# measurement-output-hw.net
KiCad netlist of a schematic drawn in Altium Designer
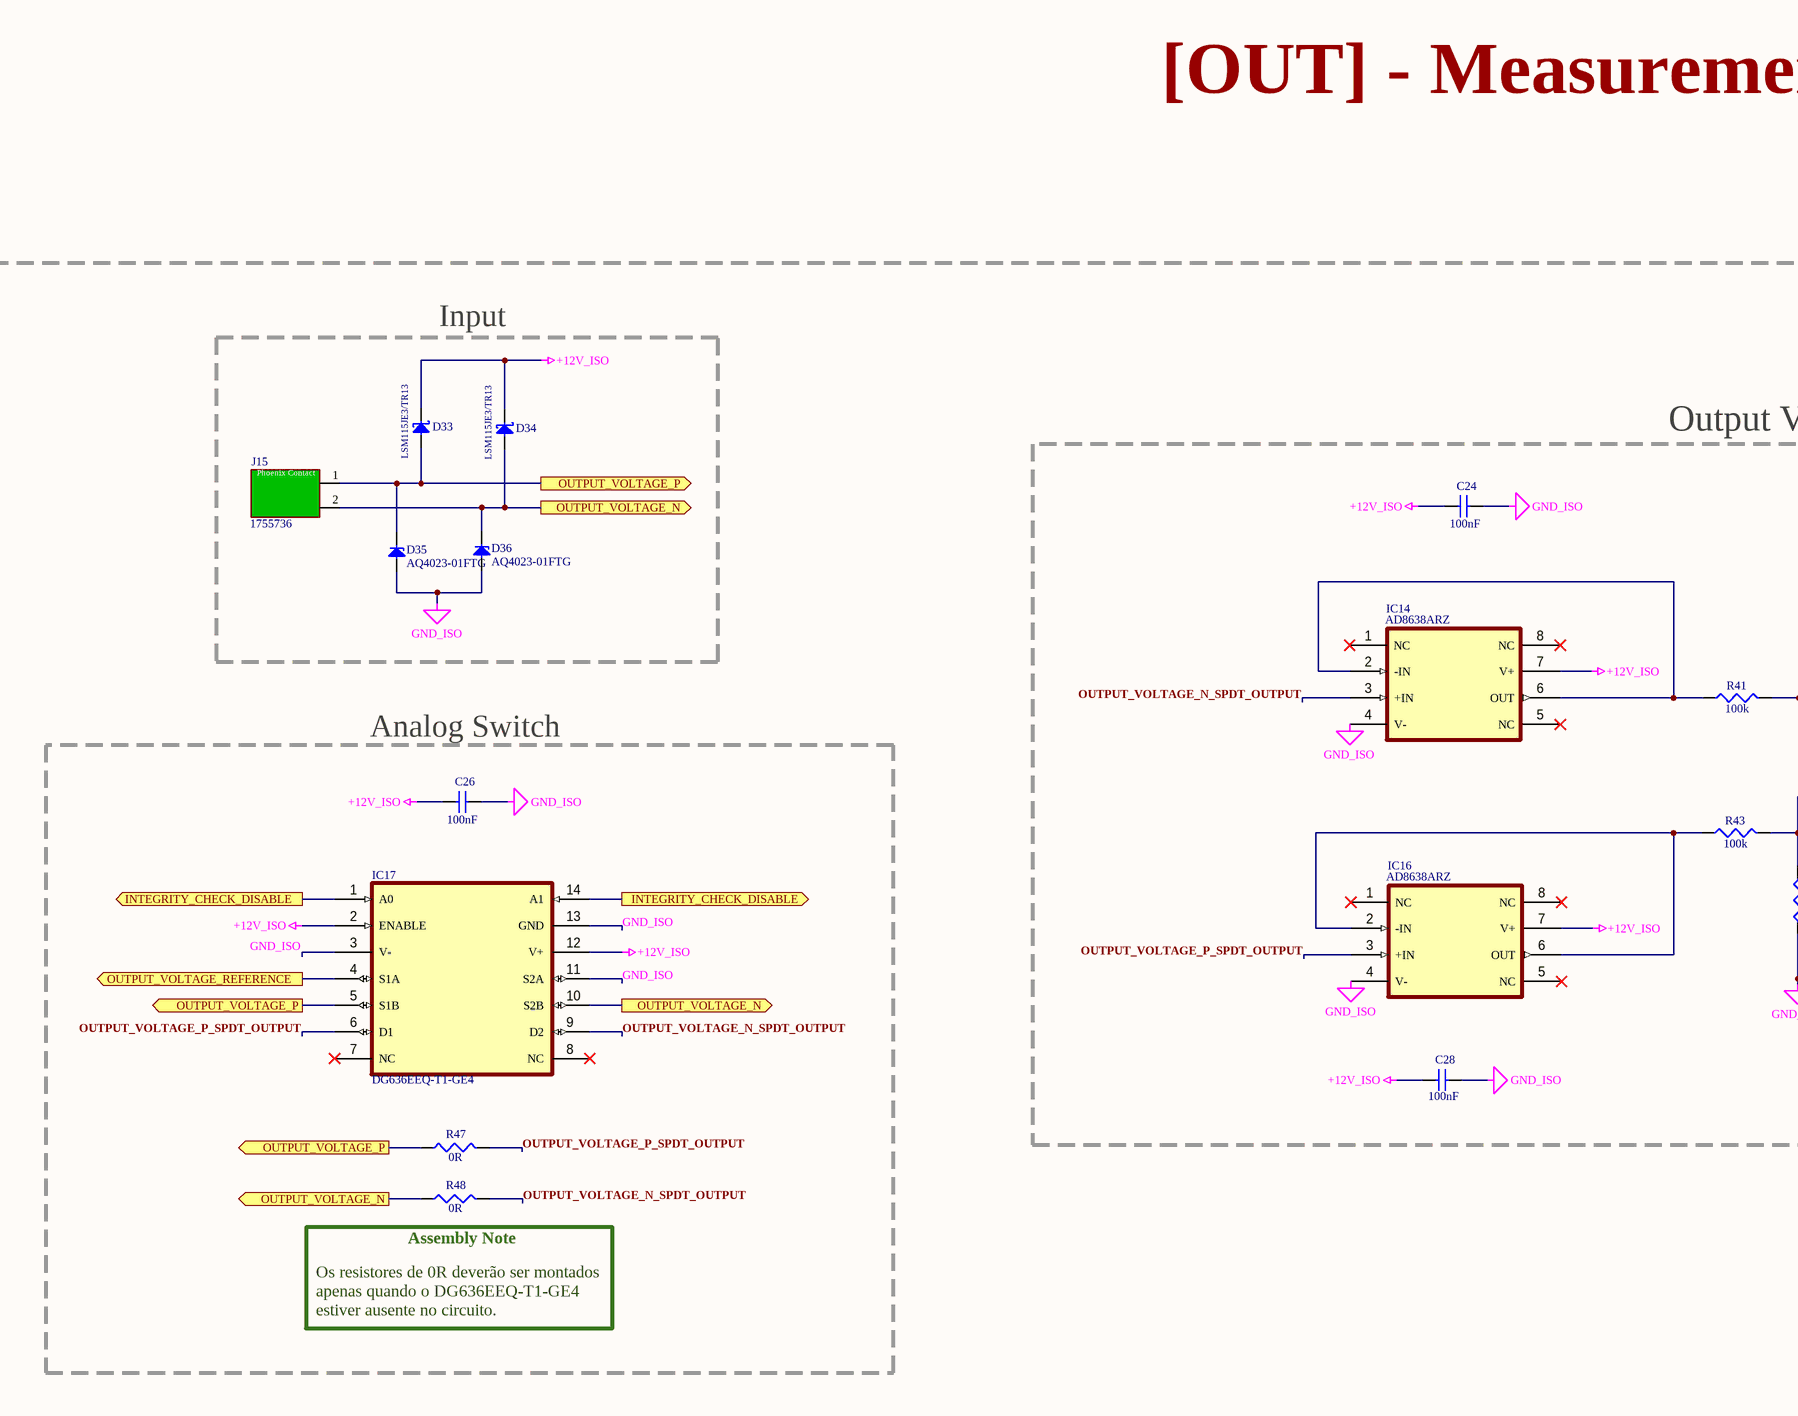
[diagram p0: measurement-output-hw.SchDoc, top left]
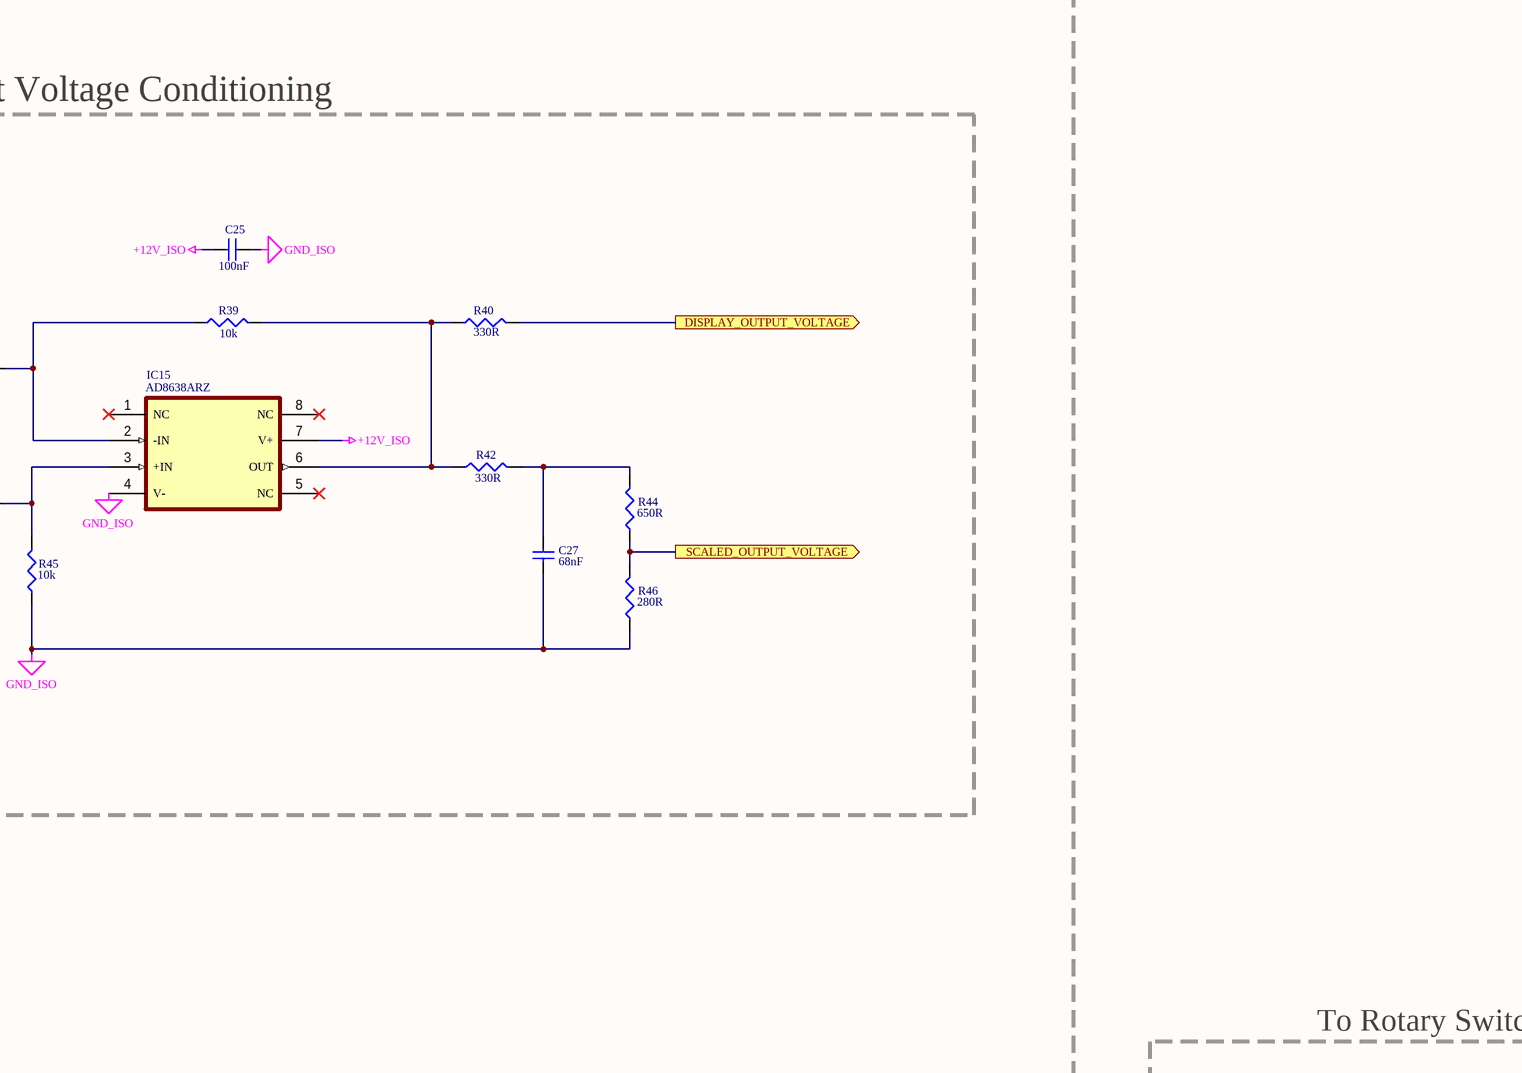
[diagram p1: measurement-output-hw.SchDoc, top right]
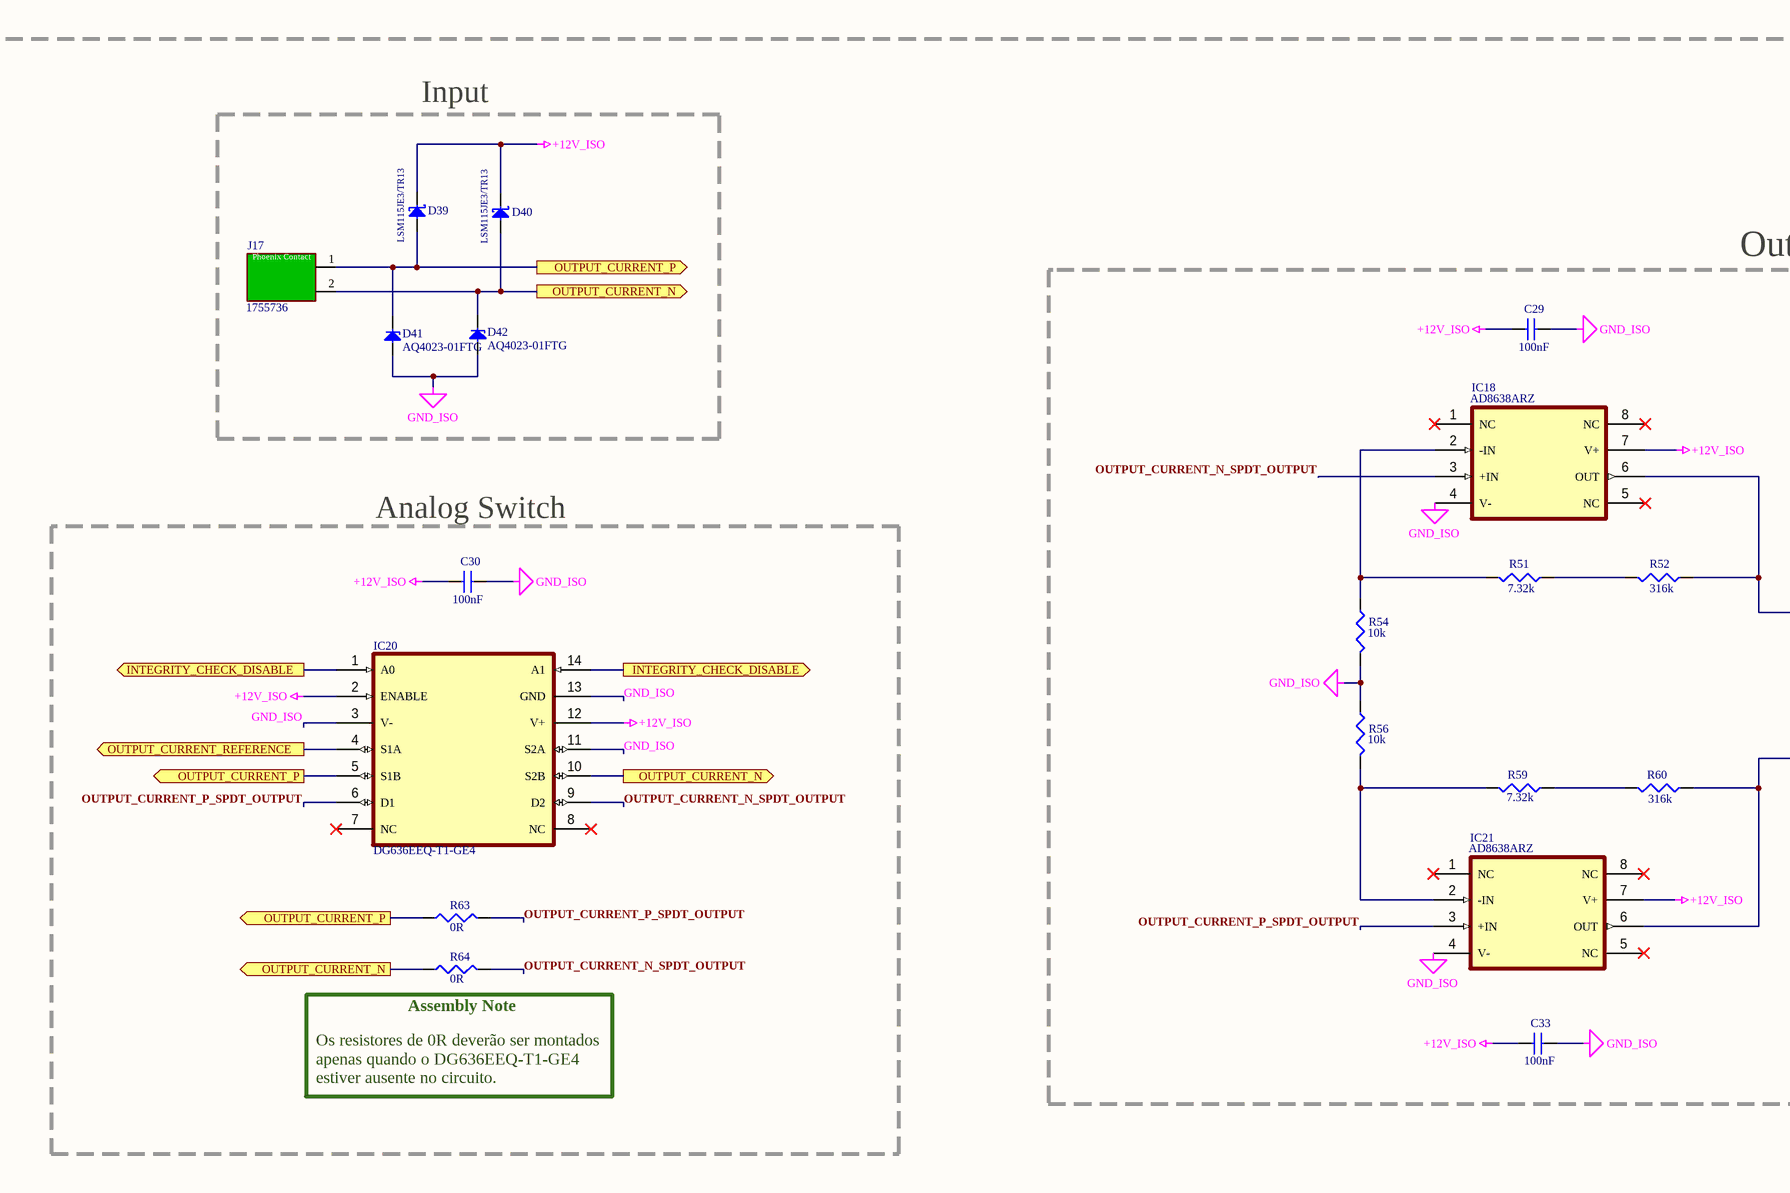
[diagram p2: measurement-output-hw.SchDoc, bottom left]
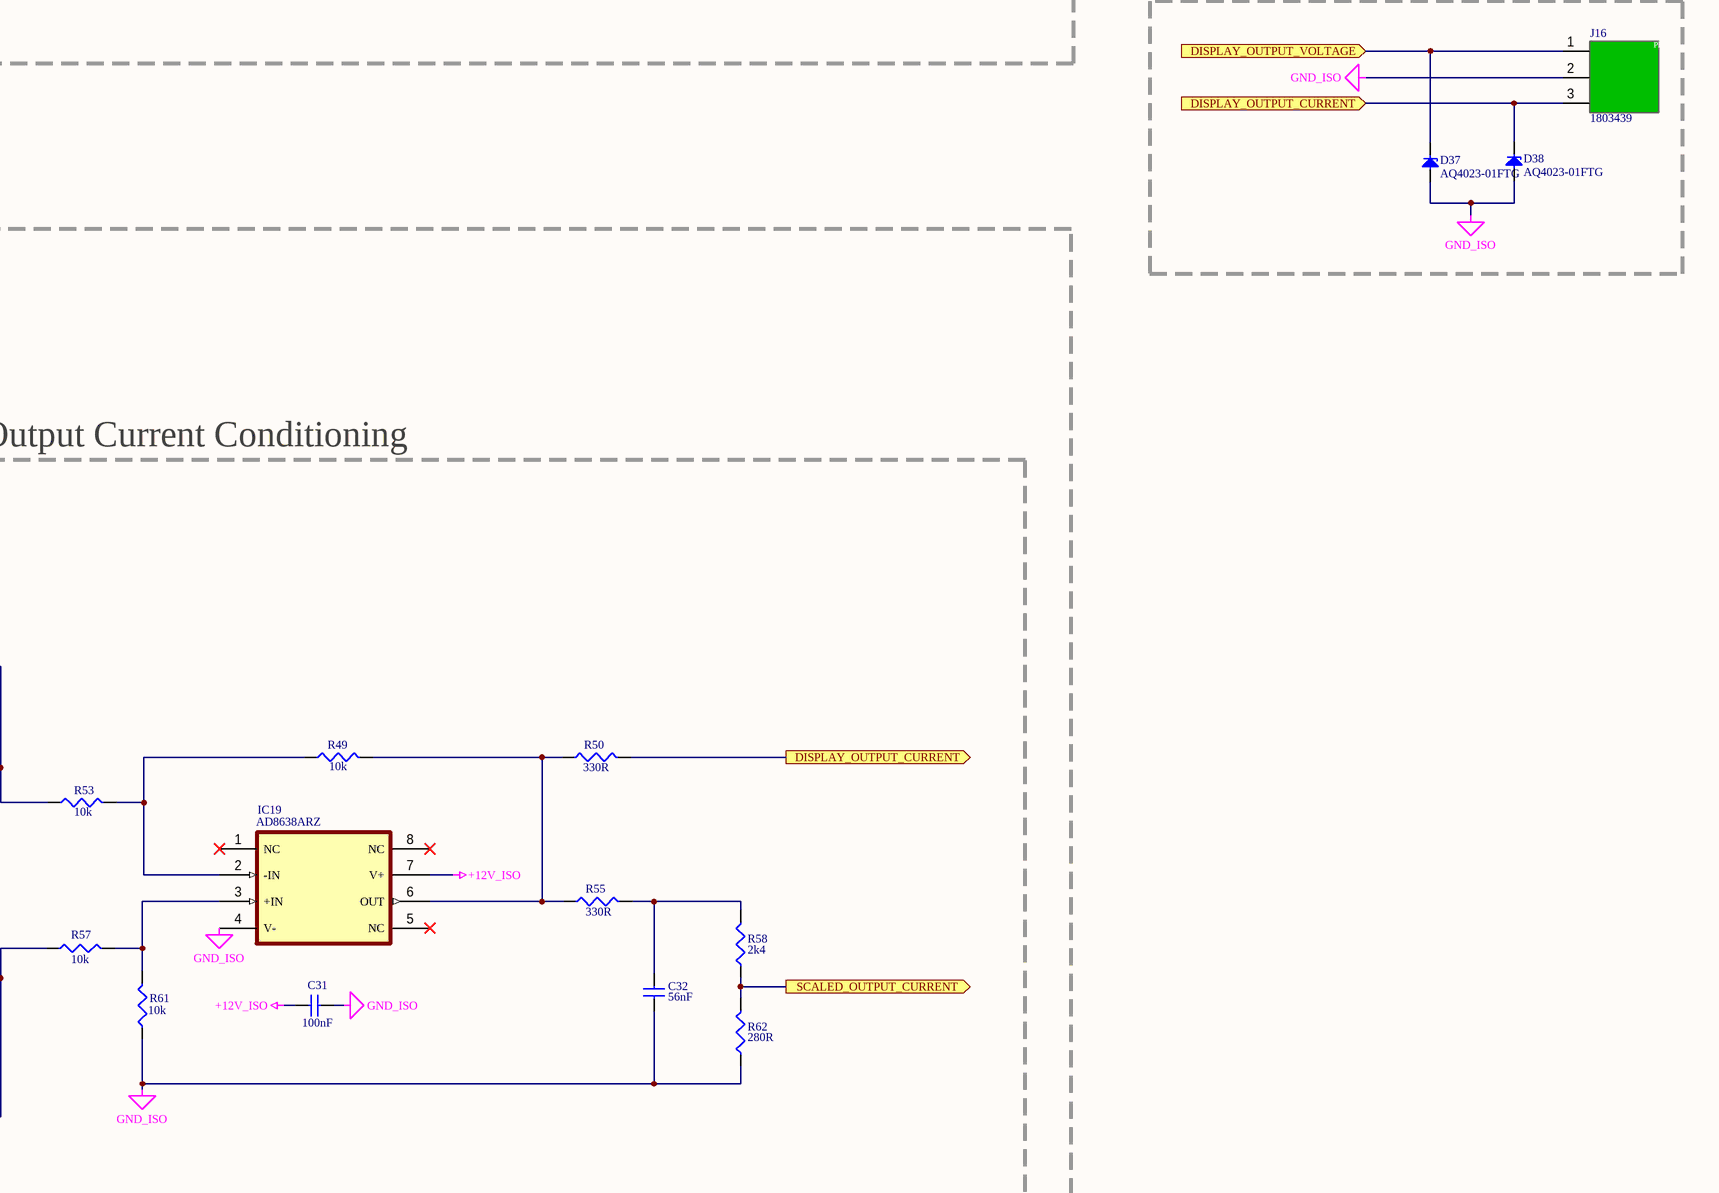
[diagram p3: measurement-output-hw.SchDoc, bottom right]

(export (version "E")
  (design (tool "Eeschema 10.0.6"))
  (components
    (comp (ref "C24")
      (value "100nF")
      (footprint "C0805")
      (libsource (lib "acopians-powerspy-monitoring-hw-library-schematic") (part "Capacitor 100nF"))
    )
    (comp (ref "C25")
      (value "100nF")
      (footprint "C0805")
      (libsource (lib "acopians-powerspy-monitoring-hw-library-schematic") (part "Capacitor 100nF"))
    )
    (comp (ref "C26")
      (value "100nF")
      (footprint "C0805")
      (libsource (lib "acopians-powerspy-monitoring-hw-library-schematic") (part "Capacitor 100nF"))
    )
    (comp (ref "C27")
      (value "68nF")
      (footprint "C0805")
      (libsource (lib "acopians-powerspy-monitoring-hw-library-schematic") (part "Capacitor 68nF"))
    )
    (comp (ref "C28")
      (value "100nF")
      (footprint "C0805")
      (libsource (lib "acopians-powerspy-monitoring-hw-library-schematic") (part "Capacitor 100nF"))
    )
    (comp (ref "C29")
      (value "100nF")
      (footprint "C0805")
      (libsource (lib "acopians-powerspy-monitoring-hw-library-schematic") (part "Capacitor 100nF"))
    )
    (comp (ref "C30")
      (value "100nF")
      (footprint "C0805")
      (libsource (lib "acopians-powerspy-monitoring-hw-library-schematic") (part "Capacitor 100nF"))
    )
    (comp (ref "C31")
      (value "100nF")
      (footprint "C0805")
      (libsource (lib "acopians-powerspy-monitoring-hw-library-schematic") (part "Capacitor 100nF"))
    )
    (comp (ref "C32")
      (value "56nF")
      (footprint "C0805")
      (libsource (lib "acopians-powerspy-monitoring-hw-library-schematic") (part "Capacitor 56nF"))
    )
    (comp (ref "C33")
      (value "100nF")
      (footprint "C0805")
      (libsource (lib "acopians-powerspy-monitoring-hw-library-schematic") (part "Capacitor 100nF"))
    )
    (comp (ref "D33")
      (value "LSM115JE3/TR13")
      (footprint "DO-214BA")
      (description "DIODE SCHOTTKY 15V, 1A, DO214BA")
      (libsource (lib "acopians-powerspy-monitoring-hw-library-schematic") (part "LSM115JE3/TR13"))
    )
    (comp (ref "D34")
      (value "LSM115JE3/TR13")
      (footprint "DO-214BA")
      (description "DIODE SCHOTTKY 15V, 1A, DO214BA")
      (libsource (lib "acopians-powerspy-monitoring-hw-library-schematic") (part "LSM115JE3/TR13"))
    )
    (comp (ref "D35")
      (value "AQ4023-01FTG")
      (footprint "SOD-323")
      (description "Unidirectional TVS DIode, 12A, 1.3pF")
      (libsource (lib "acopians-powerspy-monitoring-hw-library-schematic") (part "AQ4023-01FTG"))
    )
    (comp (ref "D36")
      (value "AQ4023-01FTG")
      (footprint "SOD-323")
      (description "Unidirectional TVS DIode, 12A, 1.3pF")
      (libsource (lib "acopians-powerspy-monitoring-hw-library-schematic") (part "AQ4023-01FTG"))
    )
    (comp (ref "D37")
      (value "AQ4023-01FTG")
      (footprint "SOD-323")
      (description "Unidirectional TVS DIode, 12A, 1.3pF")
      (libsource (lib "acopians-powerspy-monitoring-hw-library-schematic") (part "AQ4023-01FTG"))
    )
    (comp (ref "D38")
      (value "AQ4023-01FTG")
      (footprint "SOD-323")
      (description "Unidirectional TVS DIode, 12A, 1.3pF")
      (libsource (lib "acopians-powerspy-monitoring-hw-library-schematic") (part "AQ4023-01FTG"))
    )
    (comp (ref "D39")
      (value "LSM115JE3/TR13")
      (footprint "DO-214BA")
      (description "DIODE SCHOTTKY 15V, 1A, DO214BA")
      (libsource (lib "acopians-powerspy-monitoring-hw-library-schematic") (part "LSM115JE3/TR13"))
    )
    (comp (ref "D40")
      (value "LSM115JE3/TR13")
      (footprint "DO-214BA")
      (description "DIODE SCHOTTKY 15V, 1A, DO214BA")
      (libsource (lib "acopians-powerspy-monitoring-hw-library-schematic") (part "LSM115JE3/TR13"))
    )
    (comp (ref "D41")
      (value "AQ4023-01FTG")
      (footprint "SOD-323")
      (description "Unidirectional TVS DIode, 12A, 1.3pF")
      (libsource (lib "acopians-powerspy-monitoring-hw-library-schematic") (part "AQ4023-01FTG"))
    )
    (comp (ref "D42")
      (value "AQ4023-01FTG")
      (footprint "SOD-323")
      (description "Unidirectional TVS DIode, 12A, 1.3pF")
      (libsource (lib "acopians-powerspy-monitoring-hw-library-schematic") (part "AQ4023-01FTG"))
    )
    (comp (ref "IC14")
      (value "AD8638ARZ")
      (footprint "SOIC-8")
      (description "16V, Auto-Zero, Rail-to-Rail Output Operational Amplifiers")
      (libsource (lib "acopians-powerspy-monitoring-hw-library-schematic") (part "AD8638ARZ"))
    )
    (comp (ref "IC15")
      (value "AD8638ARZ")
      (footprint "SOIC-8")
      (description "16V, Auto-Zero, Rail-to-Rail Output Operational Amplifiers")
      (libsource (lib "acopians-powerspy-monitoring-hw-library-schematic") (part "AD8638ARZ"))
    )
    (comp (ref "IC16")
      (value "AD8638ARZ")
      (footprint "SOIC-8")
      (description "16V, Auto-Zero, Rail-to-Rail Output Operational Amplifiers")
      (libsource (lib "acopians-powerspy-monitoring-hw-library-schematic") (part "AD8638ARZ"))
    )
    (comp (ref "IC17")
      (value "DG636EEQ-T1-GE4")
      (footprint "TSSOP-14")
      (description "Analog Switch Dual-SPDT, 14 pins")
      (libsource (lib "acopians-powerspy-monitoring-hw-library-schematic") (part "DG636EEQ-T1-GE4"))
    )
    (comp (ref "IC18")
      (value "AD8638ARZ")
      (footprint "SOIC-8")
      (description "16V, Auto-Zero, Rail-to-Rail Output Operational Amplifiers")
      (libsource (lib "acopians-powerspy-monitoring-hw-library-schematic") (part "AD8638ARZ"))
    )
    (comp (ref "IC19")
      (value "AD8638ARZ")
      (footprint "SOIC-8")
      (description "16V, Auto-Zero, Rail-to-Rail Output Operational Amplifiers")
      (libsource (lib "acopians-powerspy-monitoring-hw-library-schematic") (part "AD8638ARZ"))
    )
    (comp (ref "IC20")
      (value "DG636EEQ-T1-GE4")
      (footprint "TSSOP-14")
      (description "Analog Switch Dual-SPDT, 14 pins")
      (libsource (lib "acopians-powerspy-monitoring-hw-library-schematic") (part "DG636EEQ-T1-GE4"))
    )
    (comp (ref "IC21")
      (value "AD8638ARZ")
      (footprint "SOIC-8")
      (description "16V, Auto-Zero, Rail-to-Rail Output Operational Amplifiers")
      (libsource (lib "acopians-powerspy-monitoring-hw-library-schematic") (part "AD8638ARZ"))
    )
    (comp (ref "J15")
      (value "1755736")
      (footprint "Conector 2 vias")
      (description "Term Block HDR 2POS VERT 5.08MM")
      (libsource (lib "acopians-powerspy-monitoring-hw-library-schematic") (part "Phoenix 1755736"))
    )
    (comp (ref "J16")
      (value "1803439")
      (footprint "Conector Phoenix 3 vias")
      (libsource (lib "acopians-powerspy-monitoring-hw-library-schematic") (part "Conector Phoenix 3 vias"))
    )
    (comp (ref "J17")
      (value "1755736")
      (footprint "Conector 2 vias")
      (description "Term Block HDR 2POS VERT 5.08MM")
      (libsource (lib "acopians-powerspy-monitoring-hw-library-schematic") (part "Phoenix 1755736"))
    )
    (comp (ref "R39")
      (value "10k")
      (footprint "Resistor 0805")
      (libsource (lib "acopians-powerspy-monitoring-hw-library-schematic") (part "Resistor 10k"))
    )
    (comp (ref "R40")
      (value "330R")
      (footprint "Resistor 0805")
      (libsource (lib "acopians-powerspy-monitoring-hw-library-schematic") (part "Resistor 330R"))
    )
    (comp (ref "R41")
      (value "100k")
      (footprint "Resistor 0805")
      (libsource (lib "acopians-powerspy-monitoring-hw-library-schematic") (part "Resistor 100k"))
    )
    (comp (ref "R42")
      (value "330R")
      (footprint "Resistor 0805")
      (libsource (lib "acopians-powerspy-monitoring-hw-library-schematic") (part "Resistor 330R"))
    )
    (comp (ref "R43")
      (value "100k")
      (footprint "Resistor 0805")
      (libsource (lib "acopians-powerspy-monitoring-hw-library-schematic") (part "Resistor 100k"))
    )
    (comp (ref "R44")
      (value "650R")
      (footprint "Resistor 0805")
      (libsource (lib "acopians-powerspy-monitoring-hw-library-schematic") (part "Resistor 650R"))
    )
    (comp (ref "R45")
      (value "10k")
      (footprint "Resistor 0805")
      (libsource (lib "acopians-powerspy-monitoring-hw-library-schematic") (part "Resistor 10k"))
    )
    (comp (ref "R46")
      (value "280R")
      (footprint "Resistor 0805")
      (libsource (lib "acopians-powerspy-monitoring-hw-library-schematic") (part "Resistor 280R"))
    )
    (comp (ref "R47")
      (value "0R")
      (footprint "Resistor 0805")
      (description "Size 0805")
      (libsource (lib "acopians-powerspy-monitoring-hw-library-schematic") (part "Resistor 0R - 0805"))
    )
    (comp (ref "R48")
      (value "0R")
      (footprint "Resistor 0805")
      (description "Size 0805")
      (libsource (lib "acopians-powerspy-monitoring-hw-library-schematic") (part "Resistor 0R - 0805"))
    )
    (comp (ref "R49")
      (value "10k")
      (footprint "Resistor 0805")
      (libsource (lib "acopians-powerspy-monitoring-hw-library-schematic") (part "Resistor 10k"))
    )
    (comp (ref "R50")
      (value "330R")
      (footprint "Resistor 0805")
      (libsource (lib "acopians-powerspy-monitoring-hw-library-schematic") (part "Resistor 330R"))
    )
    (comp (ref "R51")
      (value "7.32k")
      (footprint "Resistor 0805")
      (libsource (lib "acopians-powerspy-monitoring-hw-library-schematic") (part "Resistor 7.32k"))
    )
    (comp (ref "R52")
      (value "316k")
      (footprint "Resistor 0805")
      (libsource (lib "acopians-powerspy-monitoring-hw-library-schematic") (part "Resistor 316k"))
    )
    (comp (ref "R53")
      (value "10k")
      (footprint "Resistor 0805")
      (libsource (lib "acopians-powerspy-monitoring-hw-library-schematic") (part "Resistor 10k"))
    )
    (comp (ref "R54")
      (value "10k")
      (footprint "Resistor 0805")
      (libsource (lib "acopians-powerspy-monitoring-hw-library-schematic") (part "Resistor 10k"))
    )
    (comp (ref "R55")
      (value "330R")
      (footprint "Resistor 0805")
      (libsource (lib "acopians-powerspy-monitoring-hw-library-schematic") (part "Resistor 330R"))
    )
    (comp (ref "R56")
      (value "10k")
      (footprint "Resistor 0805")
      (libsource (lib "acopians-powerspy-monitoring-hw-library-schematic") (part "Resistor 10k"))
    )
    (comp (ref "R57")
      (value "10k")
      (footprint "Resistor 0805")
      (libsource (lib "acopians-powerspy-monitoring-hw-library-schematic") (part "Resistor 10k"))
    )
    (comp (ref "R58")
      (value "2k4")
      (footprint "Resistor 0805")
      (libsource (lib "acopians-powerspy-monitoring-hw-library-schematic") (part "Resistor 2k4"))
    )
    (comp (ref "R59")
      (value "7.32k")
      (footprint "Resistor 0805")
      (libsource (lib "acopians-powerspy-monitoring-hw-library-schematic") (part "Resistor 7.32k"))
    )
    (comp (ref "R60")
      (value "316k")
      (footprint "Resistor 0805")
      (libsource (lib "acopians-powerspy-monitoring-hw-library-schematic") (part "Resistor 316k"))
    )
    (comp (ref "R61")
      (value "10k")
      (footprint "Resistor 0805")
      (libsource (lib "acopians-powerspy-monitoring-hw-library-schematic") (part "Resistor 10k"))
    )
    (comp (ref "R62")
      (value "280R")
      (footprint "Resistor 0805")
      (libsource (lib "acopians-powerspy-monitoring-hw-library-schematic") (part "Resistor 280R"))
    )
    (comp (ref "R63")
      (value "0R")
      (footprint "Resistor 0805")
      (description "Size 0805")
      (libsource (lib "acopians-powerspy-monitoring-hw-library-schematic") (part "Resistor 0R - 0805"))
    )
    (comp (ref "R64")
      (value "0R")
      (footprint "Resistor 0805")
      (description "Size 0805")
      (libsource (lib "acopians-powerspy-monitoring-hw-library-schematic") (part "Resistor 0R - 0805"))
    )
  )
  (nets
    (net (code "1") (name "+12V_ISO") (class "Default")
      (node (ref "C24") (pin "1") (pinfunction "1_1") (pintype "passive"))
      (node (ref "C25") (pin "1") (pinfunction "1_1") (pintype "passive"))
      (node (ref "C26") (pin "1") (pinfunction "1_1") (pintype "passive"))
      (node (ref "C28") (pin "1") (pinfunction "1_1") (pintype "passive"))
      (node (ref "C29") (pin "1") (pinfunction "1_1") (pintype "passive"))
      (node (ref "C30") (pin "1") (pinfunction "1_1") (pintype "passive"))
      (node (ref "C31") (pin "1") (pinfunction "1_1") (pintype "passive"))
      (node (ref "C33") (pin "1") (pinfunction "1_1") (pintype "passive"))
      (node (ref "D33") (pin "1") (pinfunction "C_1") (pintype "passive"))
      (node (ref "D34") (pin "1") (pinfunction "C_1") (pintype "passive"))
      (node (ref "D39") (pin "1") (pinfunction "C_1") (pintype "passive"))
      (node (ref "D40") (pin "1") (pinfunction "C_1") (pintype "passive"))
      (node (ref "IC14") (pin "7") (pinfunction "V+_7") (pintype "passive"))
      (node (ref "IC15") (pin "7") (pinfunction "V+_7") (pintype "passive"))
      (node (ref "IC16") (pin "7") (pinfunction "V+_7") (pintype "passive"))
      (node (ref "IC17") (pin "12") (pinfunction "V+_12") (pintype "passive"))
      (node (ref "IC17") (pin "2") (pinfunction "ENABLE_2") (pintype "input"))
      (node (ref "IC18") (pin "7") (pinfunction "V+_7") (pintype "passive"))
      (node (ref "IC19") (pin "7") (pinfunction "V+_7") (pintype "passive"))
      (node (ref "IC20") (pin "12") (pinfunction "V+_12") (pintype "passive"))
      (node (ref "IC20") (pin "2") (pinfunction "ENABLE_2") (pintype "input"))
      (node (ref "IC21") (pin "7") (pinfunction "V+_7") (pintype "passive"))
    )
    (net (code "2") (name "/DISPLAY_OUTPUT_CURRENT") (class "Default")
      (node (ref "D38") (pin "1") (pintype "passive"))
      (node (ref "J16") (pin "3") (pinfunction "3_3") (pintype "passive"))
      (node (ref "R50") (pin "2") (pinfunction "2_2") (pintype "passive"))
    )
    (net (code "3") (name "/DISPLAY_OUTPUT_VOLTAGE") (class "Default")
      (node (ref "D37") (pin "1") (pintype "passive"))
      (node (ref "J16") (pin "1") (pinfunction "1_1") (pintype "passive"))
      (node (ref "R40") (pin "2") (pinfunction "2_2") (pintype "passive"))
    )
    (net (code "4") (name "/INTEGRITY_CHECK_DISABLE") (class "Default")
      (node (ref "IC17") (pin "1") (pinfunction "A0_1") (pintype "input"))
      (node (ref "IC17") (pin "14") (pinfunction "A1_14") (pintype "input"))
      (node (ref "IC20") (pin "1") (pinfunction "A0_1") (pintype "input"))
      (node (ref "IC20") (pin "14") (pinfunction "A1_14") (pintype "input"))
    )
    (net (code "5") (name "/OUTPUT_CURRENT_N") (class "Default")
      (node (ref "D40") (pin "2") (pinfunction "A_2") (pintype "passive"))
      (node (ref "D42") (pin "1") (pintype "passive"))
      (node (ref "IC20") (pin "10") (pinfunction "S2B_10") (pintype "bidirectional"))
      (node (ref "J17") (pin "2") (pinfunction "2_2") (pintype "passive"))
      (node (ref "R64") (pin "1") (pinfunction "1_1") (pintype "passive"))
    )
    (net (code "6") (name "/OUTPUT_CURRENT_N_SPDT_OUTPUT") (class "Default")
      (node (ref "IC18") (pin "3") (pinfunction "+IN_3") (pintype "input"))
      (node (ref "IC20") (pin "9") (pinfunction "D2_9") (pintype "bidirectional"))
      (node (ref "R64") (pin "2") (pinfunction "2_2") (pintype "passive"))
    )
    (net (code "7") (name "/OUTPUT_CURRENT_P") (class "Default")
      (node (ref "D39") (pin "2") (pinfunction "A_2") (pintype "passive"))
      (node (ref "D41") (pin "1") (pintype "passive"))
      (node (ref "IC20") (pin "5") (pinfunction "S1B_5") (pintype "bidirectional"))
      (node (ref "J17") (pin "1") (pinfunction "1_1") (pintype "passive"))
      (node (ref "R63") (pin "1") (pinfunction "1_1") (pintype "passive"))
    )
    (net (code "8") (name "/OUTPUT_CURRENT_P_SPDT_OUTPUT") (class "Default")
      (node (ref "IC20") (pin "6") (pinfunction "D1_6") (pintype "bidirectional"))
      (node (ref "IC21") (pin "3") (pinfunction "+IN_3") (pintype "input"))
      (node (ref "R63") (pin "2") (pinfunction "2_2") (pintype "passive"))
    )
    (net (code "9") (name "/OUTPUT_CURRENT_REFERENCE") (class "Default")
      (node (ref "IC20") (pin "4") (pinfunction "S1A_4") (pintype "bidirectional"))
    )
    (net (code "10") (name "/OUTPUT_VOLTAGE_N") (class "Default")
      (node (ref "D34") (pin "2") (pinfunction "A_2") (pintype "passive"))
      (node (ref "D36") (pin "1") (pintype "passive"))
      (node (ref "IC17") (pin "10") (pinfunction "S2B_10") (pintype "bidirectional"))
      (node (ref "J15") (pin "2") (pinfunction "2_2") (pintype "passive"))
      (node (ref "R48") (pin "1") (pinfunction "1_1") (pintype "passive"))
    )
    (net (code "11") (name "/OUTPUT_VOLTAGE_N_SPDT_OUTPUT") (class "Default")
      (node (ref "IC14") (pin "3") (pinfunction "+IN_3") (pintype "input"))
      (node (ref "IC17") (pin "9") (pinfunction "D2_9") (pintype "bidirectional"))
      (node (ref "R48") (pin "2") (pinfunction "2_2") (pintype "passive"))
    )
    (net (code "12") (name "/OUTPUT_VOLTAGE_P") (class "Default")
      (node (ref "D33") (pin "2") (pinfunction "A_2") (pintype "passive"))
      (node (ref "D35") (pin "1") (pintype "passive"))
      (node (ref "IC17") (pin "5") (pinfunction "S1B_5") (pintype "bidirectional"))
      (node (ref "J15") (pin "1") (pinfunction "1_1") (pintype "passive"))
      (node (ref "R47") (pin "1") (pinfunction "1_1") (pintype "passive"))
    )
    (net (code "13") (name "/OUTPUT_VOLTAGE_P_SPDT_OUTPUT") (class "Default")
      (node (ref "IC16") (pin "3") (pinfunction "+IN_3") (pintype "input"))
      (node (ref "IC17") (pin "6") (pinfunction "D1_6") (pintype "bidirectional"))
      (node (ref "R47") (pin "2") (pinfunction "2_2") (pintype "passive"))
    )
    (net (code "14") (name "/OUTPUT_VOLTAGE_REFERENCE") (class "Default")
      (node (ref "IC17") (pin "4") (pinfunction "S1A_4") (pintype "bidirectional"))
    )
    (net (code "15") (name "/SCALED_OUTPUT_CURRENT") (class "Default")
      (node (ref "R58") (pin "1") (pinfunction "1_1") (pintype "passive"))
      (node (ref "R62") (pin "2") (pinfunction "2_2") (pintype "passive"))
    )
    (net (code "16") (name "/SCALED_OUTPUT_VOLTAGE") (class "Default")
      (node (ref "R44") (pin "1") (pinfunction "1_1") (pintype "passive"))
      (node (ref "R46") (pin "2") (pinfunction "2_2") (pintype "passive"))
    )
    (net (code "17") (name "GND_ISO") (class "Default")
      (node (ref "C24") (pin "2") (pinfunction "2_2") (pintype "passive"))
      (node (ref "C25") (pin "2") (pinfunction "2_2") (pintype "passive"))
      (node (ref "C26") (pin "2") (pinfunction "2_2") (pintype "passive"))
      (node (ref "C27") (pin "1") (pinfunction "1_1") (pintype "passive"))
      (node (ref "C28") (pin "2") (pinfunction "2_2") (pintype "passive"))
      (node (ref "C29") (pin "2") (pinfunction "2_2") (pintype "passive"))
      (node (ref "C30") (pin "2") (pinfunction "2_2") (pintype "passive"))
      (node (ref "C31") (pin "2") (pinfunction "2_2") (pintype "passive"))
      (node (ref "C32") (pin "1") (pinfunction "1_1") (pintype "passive"))
      (node (ref "C33") (pin "2") (pinfunction "2_2") (pintype "passive"))
      (node (ref "D35") (pin "2") (pintype "passive"))
      (node (ref "D36") (pin "2") (pintype "passive"))
      (node (ref "D37") (pin "2") (pintype "passive"))
      (node (ref "D38") (pin "2") (pintype "passive"))
      (node (ref "D41") (pin "2") (pintype "passive"))
      (node (ref "D42") (pin "2") (pintype "passive"))
      (node (ref "IC14") (pin "4") (pinfunction "V-_4") (pintype "passive"))
      (node (ref "IC15") (pin "4") (pinfunction "V-_4") (pintype "passive"))
      (node (ref "IC16") (pin "4") (pinfunction "V-_4") (pintype "passive"))
      (node (ref "IC17") (pin "11") (pinfunction "S2A_11") (pintype "bidirectional"))
      (node (ref "IC17") (pin "13") (pinfunction "GND_13") (pintype "passive"))
      (node (ref "IC17") (pin "3") (pinfunction "V-_3") (pintype "passive"))
      (node (ref "IC18") (pin "4") (pinfunction "V-_4") (pintype "passive"))
      (node (ref "IC19") (pin "4") (pinfunction "V-_4") (pintype "passive"))
      (node (ref "IC20") (pin "11") (pinfunction "S2A_11") (pintype "bidirectional"))
      (node (ref "IC20") (pin "13") (pinfunction "GND_13") (pintype "passive"))
      (node (ref "IC20") (pin "3") (pinfunction "V-_3") (pintype "passive"))
      (node (ref "IC21") (pin "4") (pinfunction "V-_4") (pintype "passive"))
      (node (ref "J16") (pin "2") (pinfunction "2_2") (pintype "passive"))
      (node (ref "R45") (pin "1") (pinfunction "1_1") (pintype "passive"))
      (node (ref "R46") (pin "1") (pinfunction "1_1") (pintype "passive"))
      (node (ref "R54") (pin "2") (pinfunction "2_2") (pintype "passive"))
      (node (ref "R56") (pin "1") (pinfunction "1_1") (pintype "passive"))
      (node (ref "R61") (pin "1") (pinfunction "1_1") (pintype "passive"))
      (node (ref "R62") (pin "1") (pinfunction "1_1") (pintype "passive"))
    )
    (net (code "18") (name "Net-(C27-Pad2)") (class "Default")
      (node (ref "C27") (pin "2") (pinfunction "2_2") (pintype "passive"))
      (node (ref "R42") (pin "2") (pinfunction "2_2") (pintype "passive"))
      (node (ref "R44") (pin "2") (pinfunction "2_2") (pintype "passive"))
    )
    (net (code "19") (name "Net-(C32-Pad2)") (class "Default")
      (node (ref "C32") (pin "2") (pinfunction "2_2") (pintype "passive"))
      (node (ref "R55") (pin "2") (pinfunction "2_2") (pintype "passive"))
      (node (ref "R58") (pin "2") (pinfunction "2_2") (pintype "passive"))
    )
    (net (code "20") (name "Net-(IC14--IN)") (class "Default")
      (node (ref "IC14") (pin "2") (pinfunction "-IN_2") (pintype "input"))
      (node (ref "IC14") (pin "6") (pinfunction "OUT_6") (pintype "output"))
      (node (ref "R41") (pin "1") (pinfunction "1_1") (pintype "passive"))
    )
    (net (code "21") (name "Net-(IC15-+IN)") (class "Default")
      (node (ref "IC15") (pin "3") (pinfunction "+IN_3") (pintype "input"))
      (node (ref "R43") (pin "2") (pinfunction "2_2") (pintype "passive"))
      (node (ref "R45") (pin "2") (pinfunction "2_2") (pintype "passive"))
    )
    (net (code "22") (name "Net-(IC15--IN)") (class "Default")
      (node (ref "IC15") (pin "2") (pinfunction "-IN_2") (pintype "input"))
      (node (ref "R39") (pin "1") (pinfunction "1_1") (pintype "passive"))
      (node (ref "R41") (pin "2") (pinfunction "2_2") (pintype "passive"))
    )
    (net (code "23") (name "Net-(IC15-OUT)") (class "Default")
      (node (ref "IC15") (pin "6") (pinfunction "OUT_6") (pintype "output"))
      (node (ref "R39") (pin "2") (pinfunction "2_2") (pintype "passive"))
      (node (ref "R40") (pin "1") (pinfunction "1_1") (pintype "passive"))
      (node (ref "R42") (pin "1") (pinfunction "1_1") (pintype "passive"))
    )
    (net (code "24") (name "Net-(IC16--IN)") (class "Default")
      (node (ref "IC16") (pin "2") (pinfunction "-IN_2") (pintype "input"))
      (node (ref "IC16") (pin "6") (pinfunction "OUT_6") (pintype "output"))
      (node (ref "R43") (pin "1") (pinfunction "1_1") (pintype "passive"))
    )
    (net (code "25") (name "Net-(IC18--IN)") (class "Default")
      (node (ref "IC18") (pin "2") (pinfunction "-IN_2") (pintype "input"))
      (node (ref "R51") (pin "1") (pinfunction "1_1") (pintype "passive"))
      (node (ref "R54") (pin "1") (pinfunction "1_1") (pintype "passive"))
    )
    (net (code "26") (name "Net-(IC18-OUT)") (class "Default")
      (node (ref "IC18") (pin "6") (pinfunction "OUT_6") (pintype "output"))
      (node (ref "R52") (pin "2") (pinfunction "2_2") (pintype "passive"))
      (node (ref "R53") (pin "1") (pinfunction "1_1") (pintype "passive"))
    )
    (net (code "27") (name "Net-(IC19-+IN)") (class "Default")
      (node (ref "IC19") (pin "3") (pinfunction "+IN_3") (pintype "input"))
      (node (ref "R57") (pin "2") (pinfunction "2_2") (pintype "passive"))
      (node (ref "R61") (pin "2") (pinfunction "2_2") (pintype "passive"))
    )
    (net (code "28") (name "Net-(IC19--IN)") (class "Default")
      (node (ref "IC19") (pin "2") (pinfunction "-IN_2") (pintype "input"))
      (node (ref "R49") (pin "1") (pinfunction "1_1") (pintype "passive"))
      (node (ref "R53") (pin "2") (pinfunction "2_2") (pintype "passive"))
    )
    (net (code "29") (name "Net-(IC19-OUT)") (class "Default")
      (node (ref "IC19") (pin "6") (pinfunction "OUT_6") (pintype "output"))
      (node (ref "R49") (pin "2") (pinfunction "2_2") (pintype "passive"))
      (node (ref "R50") (pin "1") (pinfunction "1_1") (pintype "passive"))
      (node (ref "R55") (pin "1") (pinfunction "1_1") (pintype "passive"))
    )
    (net (code "30") (name "Net-(IC21--IN)") (class "Default")
      (node (ref "IC21") (pin "2") (pinfunction "-IN_2") (pintype "input"))
      (node (ref "R56") (pin "2") (pinfunction "2_2") (pintype "passive"))
      (node (ref "R59") (pin "1") (pinfunction "1_1") (pintype "passive"))
    )
    (net (code "31") (name "Net-(IC21-OUT)") (class "Default")
      (node (ref "IC21") (pin "6") (pinfunction "OUT_6") (pintype "output"))
      (node (ref "R57") (pin "1") (pinfunction "1_1") (pintype "passive"))
      (node (ref "R60") (pin "2") (pinfunction "2_2") (pintype "passive"))
    )
    (net (code "32") (name "Net-(R51-Pad2)") (class "Default")
      (node (ref "R51") (pin "2") (pinfunction "2_2") (pintype "passive"))
      (node (ref "R52") (pin "1") (pinfunction "1_1") (pintype "passive"))
    )
    (net (code "33") (name "Net-(R59-Pad2)") (class "Default")
      (node (ref "R59") (pin "2") (pinfunction "2_2") (pintype "passive"))
      (node (ref "R60") (pin "1") (pinfunction "1_1") (pintype "passive"))
    )
    (net (code "34") (name "unconnected-(IC14-NC-Pad1)") (class "Default")
      (node (ref "IC14") (pin "1") (pinfunction "NC_1") (pintype "passive+no_connect"))
    )
    (net (code "35") (name "unconnected-(IC14-NC-Pad5)") (class "Default")
      (node (ref "IC14") (pin "5") (pinfunction "NC_5") (pintype "passive+no_connect"))
    )
    (net (code "36") (name "unconnected-(IC14-NC-Pad8)") (class "Default")
      (node (ref "IC14") (pin "8") (pinfunction "NC_8") (pintype "passive+no_connect"))
    )
    (net (code "37") (name "unconnected-(IC15-NC-Pad1)") (class "Default")
      (node (ref "IC15") (pin "1") (pinfunction "NC_1") (pintype "passive+no_connect"))
    )
    (net (code "38") (name "unconnected-(IC15-NC-Pad5)") (class "Default")
      (node (ref "IC15") (pin "5") (pinfunction "NC_5") (pintype "passive+no_connect"))
    )
    (net (code "39") (name "unconnected-(IC15-NC-Pad8)") (class "Default")
      (node (ref "IC15") (pin "8") (pinfunction "NC_8") (pintype "passive+no_connect"))
    )
    (net (code "40") (name "unconnected-(IC16-NC-Pad1)") (class "Default")
      (node (ref "IC16") (pin "1") (pinfunction "NC_1") (pintype "passive+no_connect"))
    )
    (net (code "41") (name "unconnected-(IC16-NC-Pad5)") (class "Default")
      (node (ref "IC16") (pin "5") (pinfunction "NC_5") (pintype "passive+no_connect"))
    )
    (net (code "42") (name "unconnected-(IC16-NC-Pad8)") (class "Default")
      (node (ref "IC16") (pin "8") (pinfunction "NC_8") (pintype "passive+no_connect"))
    )
    (net (code "43") (name "unconnected-(IC17-NC-Pad7)") (class "Default")
      (node (ref "IC17") (pin "7") (pinfunction "NC_7") (pintype "passive+no_connect"))
    )
    (net (code "44") (name "unconnected-(IC17-NC-Pad8)") (class "Default")
      (node (ref "IC17") (pin "8") (pinfunction "NC_8") (pintype "passive+no_connect"))
    )
    (net (code "45") (name "unconnected-(IC18-NC-Pad1)") (class "Default")
      (node (ref "IC18") (pin "1") (pinfunction "NC_1") (pintype "passive+no_connect"))
    )
    (net (code "46") (name "unconnected-(IC18-NC-Pad5)") (class "Default")
      (node (ref "IC18") (pin "5") (pinfunction "NC_5") (pintype "passive+no_connect"))
    )
    (net (code "47") (name "unconnected-(IC18-NC-Pad8)") (class "Default")
      (node (ref "IC18") (pin "8") (pinfunction "NC_8") (pintype "passive+no_connect"))
    )
    (net (code "48") (name "unconnected-(IC19-NC-Pad1)") (class "Default")
      (node (ref "IC19") (pin "1") (pinfunction "NC_1") (pintype "passive+no_connect"))
    )
    (net (code "49") (name "unconnected-(IC19-NC-Pad5)") (class "Default")
      (node (ref "IC19") (pin "5") (pinfunction "NC_5") (pintype "passive+no_connect"))
    )
    (net (code "50") (name "unconnected-(IC19-NC-Pad8)") (class "Default")
      (node (ref "IC19") (pin "8") (pinfunction "NC_8") (pintype "passive+no_connect"))
    )
    (net (code "51") (name "unconnected-(IC20-NC-Pad7)") (class "Default")
      (node (ref "IC20") (pin "7") (pinfunction "NC_7") (pintype "passive+no_connect"))
    )
    (net (code "52") (name "unconnected-(IC20-NC-Pad8)") (class "Default")
      (node (ref "IC20") (pin "8") (pinfunction "NC_8") (pintype "passive+no_connect"))
    )
    (net (code "53") (name "unconnected-(IC21-NC-Pad1)") (class "Default")
      (node (ref "IC21") (pin "1") (pinfunction "NC_1") (pintype "passive+no_connect"))
    )
    (net (code "54") (name "unconnected-(IC21-NC-Pad5)") (class "Default")
      (node (ref "IC21") (pin "5") (pinfunction "NC_5") (pintype "passive+no_connect"))
    )
    (net (code "55") (name "unconnected-(IC21-NC-Pad8)") (class "Default")
      (node (ref "IC21") (pin "8") (pinfunction "NC_8") (pintype "passive+no_connect"))
    )
  )
)
